# usbB_4pin.net
KiCad netlist of a schematic drawn in EAGLE
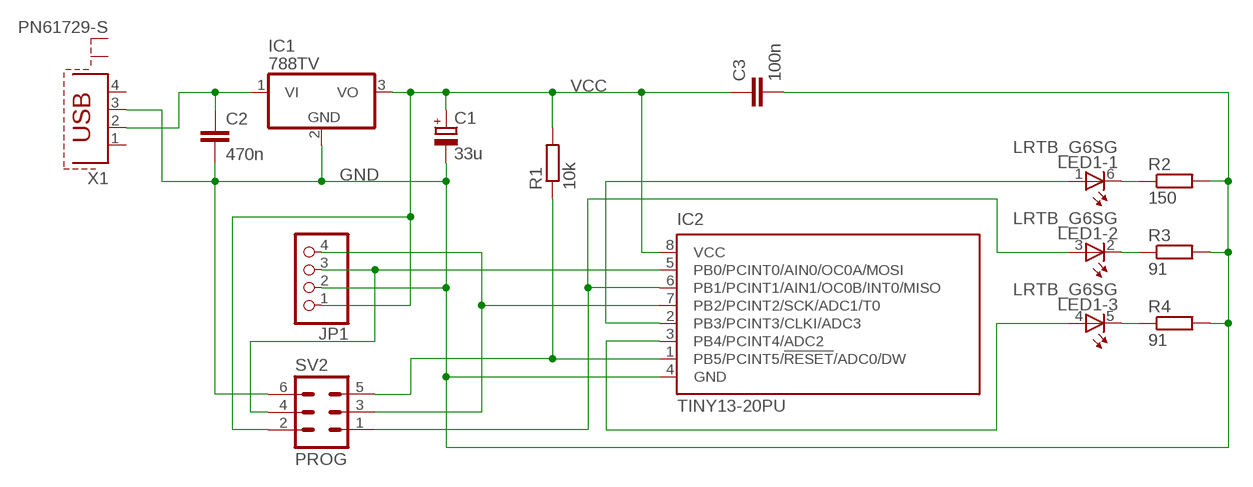
[diagram p0: schematic, sheet 1]

(export (version "E")
  (design (tool "Eeschema 10.0.6"))
  (components
    (comp (ref "C1")
      (value "33u")
      (footprint "eagle-import:E2,5-6E")
      (libsource (lib "eagle-import") (part "CPOL-EUE2,5-6E"))
    )
    (comp (ref "C2")
      (value "470n")
      (footprint "eagle-import:C050-025X075")
      (libsource (lib "eagle-import") (part "C-EU050-025X075"))
    )
    (comp (ref "C3")
      (value "100n")
      (footprint "eagle-import:C050-025X075")
      (libsource (lib "eagle-import") (part "C-EU050-025X075"))
    )
    (comp (ref "IC1")
      (value "788TV")
      (footprint "eagle-import:TO220V")
      (libsource (lib "eagle-import") (part "78TV8"))
    )
    (comp (ref "IC2")
      (value "TINY13-20PU")
      (footprint "eagle-import:DIL08")
      (fields (field (name "MPN") "ATTINY13-20PU"))
      (libsource (lib "eagle-import") (part "TINY13PU-20"))
    )
    (comp (ref "JP1")
      (value "PINHD-1X4")
      (footprint "eagle-import:1X04")
      (libsource (lib "eagle-import") (part "PINHD-1X4"))
    )
    (comp (ref "LED1")
      (value "LRTB_G6SG")
      (footprint "eagle-import:LRTB_G6SG")
      (libsource (lib "eagle-import") (part "LRTB_G6SG"))
    )
    (comp (ref "R1")
      (value "10k")
      (footprint "eagle-import:0204_7")
      (libsource (lib "eagle-import") (part "R-EU_0204/7"))
    )
    (comp (ref "R2")
      (value "150")
      (footprint "eagle-import:0204_7")
      (libsource (lib "eagle-import") (part "R-EU_0204/7"))
    )
    (comp (ref "R3")
      (value "91")
      (footprint "eagle-import:0204_7")
      (libsource (lib "eagle-import") (part "R-EU_0204/7"))
    )
    (comp (ref "R4")
      (value "91")
      (footprint "eagle-import:0204_7")
      (libsource (lib "eagle-import") (part "R-EU_0204/7"))
    )
    (comp (ref "SV2")
      (value "PROG")
      (footprint "eagle-import:ML6")
      (libsource (lib "eagle-import") (part "ML6"))
    )
    (comp (ref "X1")
      (value "PN61729-S")
      (footprint "eagle-import:PN61729-S")
      (libsource (lib "eagle-import") (part "PN61729-S"))
    )
  )
  (nets
    (net (code "1") (name "/GND") (class "Default")
      (node (ref "C1") (pin "-") (pinfunction "-_-") (pintype "passive"))
      (node (ref "C2") (pin "2") (pinfunction "2_2") (pintype "passive"))
      (node (ref "C3") (pin "2") (pinfunction "2_2") (pintype "passive"))
      (node (ref "IC1") (pin "2") (pinfunction "GND_2") (pintype "passive"))
      (node (ref "IC2") (pin "4") (pinfunction "GND_4") (pintype "power_in"))
      (node (ref "JP1") (pin "2") (pinfunction "2_2") (pintype "passive"))
      (node (ref "R2") (pin "2") (pinfunction "2_2") (pintype "passive"))
      (node (ref "R3") (pin "2") (pinfunction "2_2") (pintype "passive"))
      (node (ref "R4") (pin "2") (pinfunction "2_2") (pintype "passive"))
      (node (ref "SV2") (pin "6") (pinfunction "6_6") (pintype "passive"))
      (node (ref "X1") (pin "3") (pinfunction "3_3") (pintype "passive"))
    )
    (net (code "2") (name "/VCC") (class "Default")
      (node (ref "C1") (pin "+") (pinfunction "+_+") (pintype "passive"))
      (node (ref "C3") (pin "1") (pinfunction "1_1") (pintype "passive"))
      (node (ref "IC1") (pin "3") (pinfunction "VO_3") (pintype "passive"))
      (node (ref "IC2") (pin "8") (pinfunction "VCC_8") (pintype "power_in"))
      (node (ref "JP1") (pin "1") (pinfunction "1_1") (pintype "passive"))
      (node (ref "R1") (pin "2") (pinfunction "2_2") (pintype "passive"))
      (node (ref "SV2") (pin "2") (pinfunction "2_2") (pintype "passive"))
    )
    (net (code "3") (name "Net-(IC1-VI)") (class "Default")
      (node (ref "C2") (pin "1") (pinfunction "1_1") (pintype "passive"))
      (node (ref "IC1") (pin "1") (pinfunction "VI_1") (pintype "input"))
      (node (ref "X1") (pin "2") (pinfunction "2_2") (pintype "passive"))
    )
    (net (code "4") (name "Net-(IC2-PB0{slash}PCINT0{slash}AIN0{slash}OC0A{slash}MOSI)") (class "Default")
      (node (ref "IC2") (pin "5") (pinfunction "PB0/PCINT0/AIN0/OC0A/MOSI_5") (pintype "bidirectional"))
      (node (ref "JP1") (pin "3") (pinfunction "3_3") (pintype "passive"))
      (node (ref "SV2") (pin "4") (pinfunction "4_4") (pintype "passive"))
    )
    (net (code "5") (name "Net-(IC2-PB1{slash}PCINT1{slash}AIN1{slash}OC0B{slash}INT0{slash}MISO)") (class "Default")
      (node (ref "IC2") (pin "6") (pinfunction "PB1/PCINT1/AIN1/OC0B/INT0/MISO_6") (pintype "bidirectional"))
      (node (ref "LED1") (pin "3") (pinfunction "A_3") (pintype "passive"))
      (node (ref "SV2") (pin "1") (pinfunction "1_1") (pintype "passive"))
    )
    (net (code "6") (name "Net-(IC2-PB2{slash}PCINT2{slash}SCK{slash}ADC1{slash}T0)") (class "Default")
      (node (ref "IC2") (pin "7") (pinfunction "PB2/PCINT2/SCK/ADC1/T0_7") (pintype "bidirectional"))
      (node (ref "JP1") (pin "4") (pinfunction "4_4") (pintype "passive"))
      (node (ref "SV2") (pin "3") (pinfunction "3_3") (pintype "passive"))
    )
    (net (code "7") (name "Net-(IC2-PB3{slash}PCINT3{slash}CLKI{slash}ADC3)") (class "Default")
      (node (ref "IC2") (pin "2") (pinfunction "PB3/PCINT3/CLKI/ADC3_2") (pintype "bidirectional"))
      (node (ref "LED1") (pin "1") (pinfunction "A_1") (pintype "passive"))
    )
    (net (code "8") (name "Net-(IC2-PB4{slash}PCINT4{slash}ADC2)") (class "Default")
      (node (ref "IC2") (pin "3") (pinfunction "PB4/PCINT4/ADC2_3") (pintype "bidirectional"))
      (node (ref "LED1") (pin "4") (pinfunction "A_4") (pintype "passive"))
    )
    (net (code "9") (name "Net-(IC2-PB5{slash}PCINT5{slash}~{RESET}{slash}ADC0{slash}DW)") (class "Default")
      (node (ref "IC2") (pin "1") (pinfunction "PB5/PCINT5/~{RESET}/ADC0/DW_1") (pintype "bidirectional"))
      (node (ref "R1") (pin "1") (pinfunction "1_1") (pintype "passive"))
      (node (ref "SV2") (pin "5") (pinfunction "5_5") (pintype "passive"))
    )
    (net (code "10") (name "Net-(LED1A-C)") (class "Default")
      (node (ref "LED1") (pin "6") (pinfunction "C_6") (pintype "passive"))
      (node (ref "R2") (pin "1") (pinfunction "1_1") (pintype "passive"))
    )
    (net (code "11") (name "Net-(LED1B-C)") (class "Default")
      (node (ref "LED1") (pin "2") (pinfunction "C_2") (pintype "passive"))
      (node (ref "R3") (pin "1") (pinfunction "1_1") (pintype "passive"))
    )
    (net (code "12") (name "Net-(LED1C-C)") (class "Default")
      (node (ref "LED1") (pin "5") (pinfunction "C_5") (pintype "passive"))
      (node (ref "R4") (pin "1") (pinfunction "1_1") (pintype "passive"))
    )
    (net (code "13") (name "unconnected-(X1-Pad1)") (class "Default")
      (node (ref "X1") (pin "1") (pinfunction "1_1") (pintype "passive"))
    )
    (net (code "14") (name "unconnected-(X1-Pad4)") (class "Default")
      (node (ref "X1") (pin "4") (pinfunction "4_4") (pintype "passive"))
    )
    (net (code "15") (name "unconnected-(X1-PadS1)") (class "Default")
      (node (ref "X1") (pin "S1") (pinfunction "S1_S1") (pintype "passive"))
    )
    (net (code "16") (name "unconnected-(X1-PadS2)") (class "Default")
      (node (ref "X1") (pin "S2") (pinfunction "S2_S2") (pintype "passive"))
    )
  )
)
